# Sensor.net
KiCad netlist of a schematic drawn in EAGLE
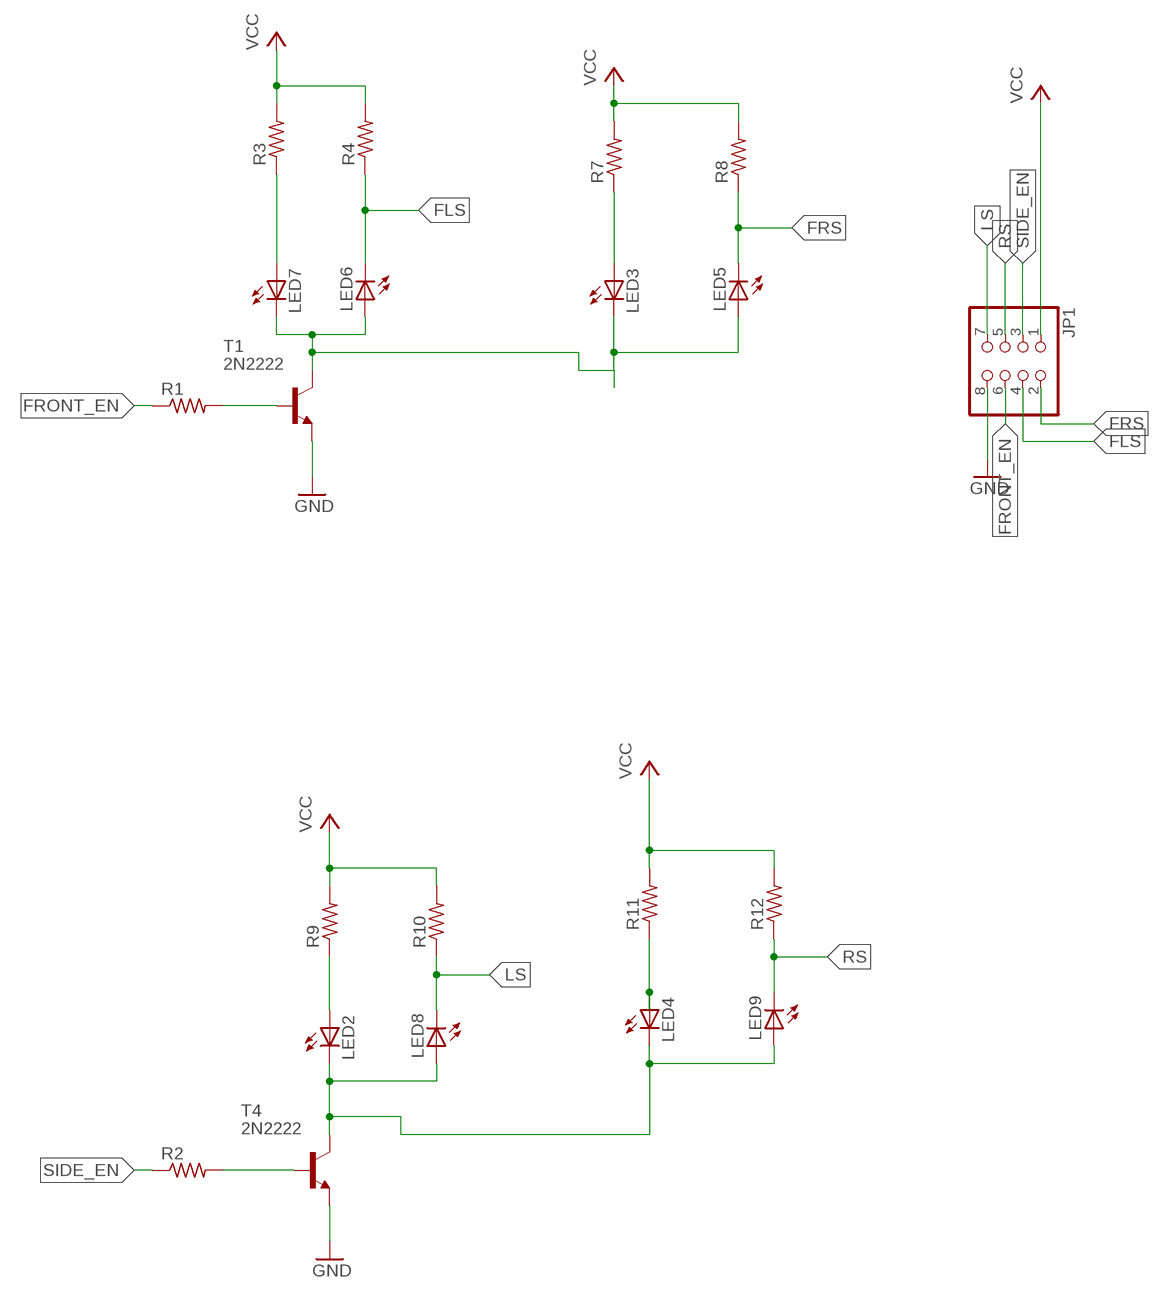
[diagram p0: schematic, sheet 1]

(export (version "E")
  (design (tool "Eeschema 10.0.6"))
  (components
    (comp (ref "JP1")
      (value "PINHD-2X4")
      (footprint "eagle-import:2X04")
      (libsource (lib "eagle-import") (part "PINHD-2X4"))
    )
    (comp (ref "LED2")
      (value "LED5MM")
      (footprint "eagle-import:LED5MM")
      (libsource (lib "eagle-import") (part "LED5MM"))
    )
    (comp (ref "LED3")
      (value "LED5MM")
      (footprint "eagle-import:LED5MM")
      (libsource (lib "eagle-import") (part "LED5MM"))
    )
    (comp (ref "LED4")
      (value "LED5MM")
      (footprint "eagle-import:LED5MM")
      (libsource (lib "eagle-import") (part "LED5MM"))
    )
    (comp (ref "LED5")
      (value "LED5MM")
      (footprint "eagle-import:LED5MM")
      (libsource (lib "eagle-import") (part "LED5MM"))
    )
    (comp (ref "LED6")
      (value "LED5MM")
      (footprint "eagle-import:LED5MM")
      (libsource (lib "eagle-import") (part "LED5MM"))
    )
    (comp (ref "LED7")
      (value "LED5MM")
      (footprint "eagle-import:LED5MM")
      (libsource (lib "eagle-import") (part "LED5MM"))
    )
    (comp (ref "LED8")
      (value "LED5MM")
      (footprint "eagle-import:LED5MM")
      (libsource (lib "eagle-import") (part "LED5MM"))
    )
    (comp (ref "LED9")
      (value "LED5MM")
      (footprint "eagle-import:LED5MM")
      (libsource (lib "eagle-import") (part "LED5MM"))
    )
    (comp (ref "R1")
      (value "R-US_R0805")
      (footprint "eagle-import:R0805")
      (libsource (lib "eagle-import") (part "R-US_R0805"))
    )
    (comp (ref "R2")
      (value "R-US_R0805")
      (footprint "eagle-import:R0805")
      (libsource (lib "eagle-import") (part "R-US_R0805"))
    )
    (comp (ref "R3")
      (value "R-US_R0805")
      (footprint "eagle-import:R0805")
      (libsource (lib "eagle-import") (part "R-US_R0805"))
    )
    (comp (ref "R4")
      (value "R-US_R0805")
      (footprint "eagle-import:R0805")
      (libsource (lib "eagle-import") (part "R-US_R0805"))
    )
    (comp (ref "R7")
      (value "R-US_R0805")
      (footprint "eagle-import:R0805")
      (libsource (lib "eagle-import") (part "R-US_R0805"))
    )
    (comp (ref "R8")
      (value "R-US_R0805")
      (footprint "eagle-import:R0805")
      (libsource (lib "eagle-import") (part "R-US_R0805"))
    )
    (comp (ref "R9")
      (value "R-US_R0805")
      (footprint "eagle-import:R0805")
      (libsource (lib "eagle-import") (part "R-US_R0805"))
    )
    (comp (ref "R10")
      (value "R-US_R0805")
      (footprint "eagle-import:R0805")
      (libsource (lib "eagle-import") (part "R-US_R0805"))
    )
    (comp (ref "R11")
      (value "R-US_R0805")
      (footprint "eagle-import:R0805")
      (libsource (lib "eagle-import") (part "R-US_R0805"))
    )
    (comp (ref "R12")
      (value "R-US_R0805")
      (footprint "eagle-import:R0805")
      (libsource (lib "eagle-import") (part "R-US_R0805"))
    )
    (comp (ref "T1")
      (value "2N2222")
      (footprint "eagle-import:TO92-EBC-OVAL")
      (libsource (lib "eagle-import") (part "2N2222"))
    )
    (comp (ref "T4")
      (value "2N2222")
      (footprint "eagle-import:TO92-EBC-OVAL")
      (libsource (lib "eagle-import") (part "2N2222"))
    )
  )
  (nets
    (net (code "1") (name "FLS") (class "Default")
      (node (ref "JP1") (pin "4") (pinfunction "4_4") (pintype "passive"))
      (node (ref "LED6") (pin "K") (pinfunction "C_K") (pintype "passive"))
      (node (ref "R4") (pin "1") (pinfunction "1_1") (pintype "passive"))
    )
    (net (code "2") (name "FRONT_EN") (class "Default")
      (node (ref "JP1") (pin "6") (pinfunction "6_6") (pintype "passive"))
      (node (ref "R1") (pin "1") (pinfunction "1_1") (pintype "passive"))
    )
    (net (code "3") (name "FRS") (class "Default")
      (node (ref "JP1") (pin "2") (pinfunction "2_2") (pintype "passive"))
      (node (ref "LED5") (pin "K") (pinfunction "C_K") (pintype "passive"))
      (node (ref "R8") (pin "1") (pinfunction "1_1") (pintype "passive"))
    )
    (net (code "4") (name "GND") (class "Default")
      (node (ref "JP1") (pin "8") (pinfunction "8_8") (pintype "passive"))
      (node (ref "T1") (pin "E") (pinfunction "E_E") (pintype "passive"))
      (node (ref "T4") (pin "E") (pinfunction "E_E") (pintype "passive"))
    )
    (net (code "5") (name "LS") (class "Default")
      (node (ref "JP1") (pin "7") (pinfunction "7_7") (pintype "passive"))
      (node (ref "LED8") (pin "K") (pinfunction "C_K") (pintype "passive"))
      (node (ref "R10") (pin "1") (pinfunction "1_1") (pintype "passive"))
    )
    (net (code "6") (name "Net-(LED2-C)") (class "Default")
      (node (ref "LED2") (pin "K") (pinfunction "C_K") (pintype "passive"))
      (node (ref "LED4") (pin "K") (pinfunction "C_K") (pintype "passive"))
      (node (ref "LED8") (pin "A") (pinfunction "A_A") (pintype "passive"))
      (node (ref "LED9") (pin "A") (pinfunction "A_A") (pintype "passive"))
      (node (ref "T4") (pin "C") (pinfunction "C_C") (pintype "passive"))
    )
    (net (code "7") (name "Net-(LED2-PadA)") (class "Default")
      (node (ref "LED2") (pin "A") (pinfunction "A_A") (pintype "passive"))
      (node (ref "R9") (pin "1") (pinfunction "1_1") (pintype "passive"))
    )
    (net (code "8") (name "Net-(LED3-C)") (class "Default")
      (node (ref "LED3") (pin "K") (pinfunction "C_K") (pintype "passive"))
      (node (ref "LED5") (pin "A") (pinfunction "A_A") (pintype "passive"))
      (node (ref "LED6") (pin "A") (pinfunction "A_A") (pintype "passive"))
      (node (ref "LED7") (pin "K") (pinfunction "C_K") (pintype "passive"))
      (node (ref "T1") (pin "C") (pinfunction "C_C") (pintype "passive"))
    )
    (net (code "9") (name "Net-(LED3-PadA)") (class "Default")
      (node (ref "LED3") (pin "A") (pinfunction "A_A") (pintype "passive"))
      (node (ref "R7") (pin "1") (pinfunction "1_1") (pintype "passive"))
    )
    (net (code "10") (name "Net-(LED4-PadA)") (class "Default")
      (node (ref "LED4") (pin "A") (pinfunction "A_A") (pintype "passive"))
      (node (ref "R11") (pin "1") (pinfunction "1_1") (pintype "passive"))
    )
    (net (code "11") (name "Net-(LED7-PadA)") (class "Default")
      (node (ref "LED7") (pin "A") (pinfunction "A_A") (pintype "passive"))
      (node (ref "R3") (pin "1") (pinfunction "1_1") (pintype "passive"))
    )
    (net (code "12") (name "Net-(R1-Pad2)") (class "Default")
      (node (ref "R1") (pin "2") (pinfunction "2_2") (pintype "passive"))
      (node (ref "T1") (pin "B") (pinfunction "B_B") (pintype "passive"))
    )
    (net (code "13") (name "Net-(R2-Pad2)") (class "Default")
      (node (ref "R2") (pin "2") (pinfunction "2_2") (pintype "passive"))
      (node (ref "T4") (pin "B") (pinfunction "B_B") (pintype "passive"))
    )
    (net (code "14") (name "RS") (class "Default")
      (node (ref "JP1") (pin "5") (pinfunction "5_5") (pintype "passive"))
      (node (ref "LED9") (pin "K") (pinfunction "C_K") (pintype "passive"))
      (node (ref "R12") (pin "1") (pinfunction "1_1") (pintype "passive"))
    )
    (net (code "15") (name "SIDE_EN") (class "Default")
      (node (ref "JP1") (pin "3") (pinfunction "3_3") (pintype "passive"))
      (node (ref "R2") (pin "1") (pinfunction "1_1") (pintype "passive"))
    )
    (net (code "16") (name "VCC") (class "Default")
      (node (ref "JP1") (pin "1") (pinfunction "1_1") (pintype "passive"))
      (node (ref "R10") (pin "2") (pinfunction "2_2") (pintype "passive"))
      (node (ref "R11") (pin "2") (pinfunction "2_2") (pintype "passive"))
      (node (ref "R12") (pin "2") (pinfunction "2_2") (pintype "passive"))
      (node (ref "R3") (pin "2") (pinfunction "2_2") (pintype "passive"))
      (node (ref "R4") (pin "2") (pinfunction "2_2") (pintype "passive"))
      (node (ref "R7") (pin "2") (pinfunction "2_2") (pintype "passive"))
      (node (ref "R8") (pin "2") (pinfunction "2_2") (pintype "passive"))
      (node (ref "R9") (pin "2") (pinfunction "2_2") (pintype "passive"))
    )
  )
)
